# caton-ads1299.net
KiCad netlist of a schematic drawn in Altium Designer
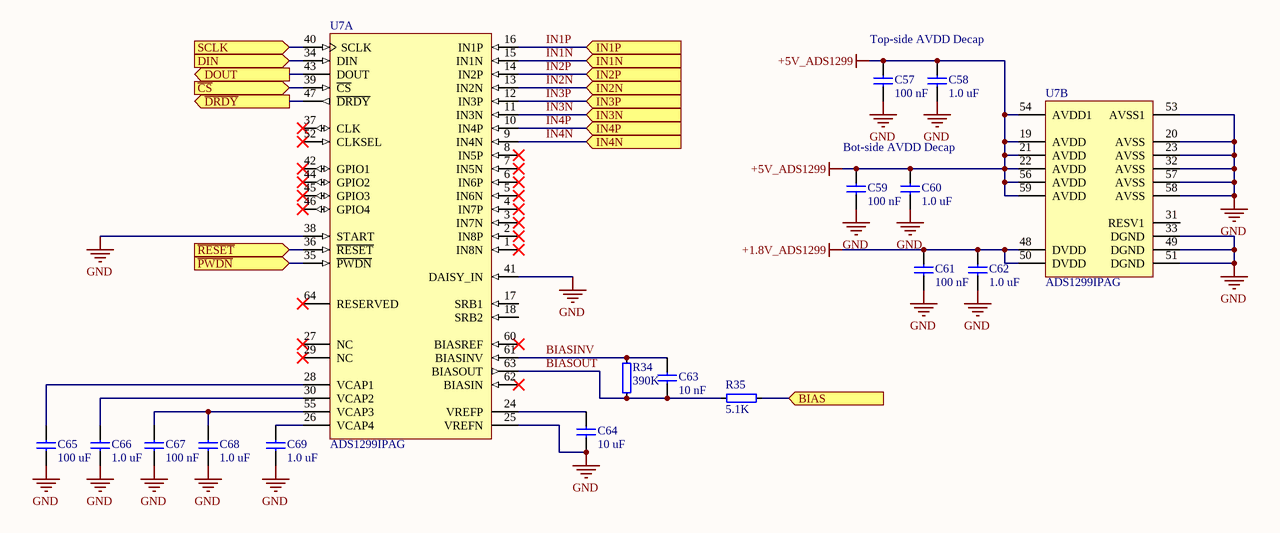
[diagram p0: caton-ads1299.SchDoc]

(export (version "E")
  (design (tool "Eeschema 10.0.6"))
  (components
    (comp (ref "C57")
      (value "100 nF")
      (footprint "BWRC:0402")
      (description "Capacitor, 0402, X5R, ±20%")
      (fields
        (field (name "PART NUMBER") "C0402-4µ7")
        (field (name "MANUFACTURER") "N.A.")
        (field (name "AUTHOR") "rsk")
      )
      (libsource (lib "BSAC") (part "C0402"))
    )
    (comp (ref "C58")
      (value "1.0 uF")
      (footprint "BWRC:0402")
      (description "Capacitor, 0402, X5R, ±20%")
      (fields
        (field (name "PART NUMBER") "C0402-4µ7")
        (field (name "MANUFACTURER") "N.A.")
        (field (name "AUTHOR") "rsk")
      )
      (libsource (lib "BSAC") (part "C0402"))
    )
    (comp (ref "C59")
      (value "100 nF")
      (footprint "BWRC:0402")
      (description "Capacitor, 0402, X5R, ±20%")
      (fields
        (field (name "PART NUMBER") "C0402-4µ7")
        (field (name "MANUFACTURER") "N.A.")
        (field (name "AUTHOR") "rsk")
      )
      (libsource (lib "BSAC") (part "C0402"))
    )
    (comp (ref "C60")
      (value "1.0 uF")
      (footprint "BWRC:0402")
      (description "Capacitor, 0402, X5R, ±20%")
      (fields
        (field (name "PART NUMBER") "C0402-4µ7")
        (field (name "MANUFACTURER") "N.A.")
        (field (name "AUTHOR") "rsk")
      )
      (libsource (lib "BSAC") (part "C0402"))
    )
    (comp (ref "C61")
      (value "100 nF")
      (footprint "BWRC:0402")
      (description "Capacitor, 0402, X5R, ±20%")
      (fields
        (field (name "PART NUMBER") "C0402-4µ7")
        (field (name "MANUFACTURER") "N.A.")
        (field (name "AUTHOR") "rsk")
      )
      (libsource (lib "BSAC") (part "C0402"))
    )
    (comp (ref "C62")
      (value "1.0 uF")
      (footprint "BWRC:0402")
      (description "Capacitor, 0402, X5R, ±20%")
      (fields
        (field (name "PART NUMBER") "C0402-4µ7")
        (field (name "MANUFACTURER") "N.A.")
        (field (name "AUTHOR") "rsk")
      )
      (libsource (lib "BSAC") (part "C0402"))
    )
    (comp (ref "C63")
      (value "10 nF")
      (footprint "BWRC:0402")
      (description "Capacitor, 0402, X5R, ±20%")
      (fields
        (field (name "PART NUMBER") "C0402-4µ7")
        (field (name "MANUFACTURER") "N.A.")
        (field (name "AUTHOR") "rsk")
      )
      (libsource (lib "BSAC") (part "C0402"))
    )
    (comp (ref "C64")
      (value "10 uF")
      (footprint "BWRC:0402")
      (description "Capacitor, 0402, X5R, ±20%")
      (fields
        (field (name "PART NUMBER") "C0402-4µ7")
        (field (name "MANUFACTURER") "N.A.")
        (field (name "AUTHOR") "rsk")
      )
      (libsource (lib "BSAC") (part "C0402"))
    )
    (comp (ref "C65")
      (value "100 uF")
      (footprint "BWRC:0805")
      (description "Capacitor, 0805")
      (fields
        (field (name "PART NUMBER") "C0603-4µ7")
        (field (name "MANUFACTURER") "N.A.")
        (field (name "AUTHOR") "rsk")
      )
      (libsource (lib "BSAC") (part "C0805"))
    )
    (comp (ref "C66")
      (value "1.0 uF")
      (footprint "BWRC:0402")
      (description "Capacitor, 0402, X5R, ±20%")
      (fields
        (field (name "PART NUMBER") "C0402-4µ7")
        (field (name "MANUFACTURER") "N.A.")
        (field (name "AUTHOR") "rsk")
      )
      (libsource (lib "BSAC") (part "C0402"))
    )
    (comp (ref "C67")
      (value "100 nF")
      (footprint "BWRC:0402")
      (description "Capacitor, 0402, X5R, ±20%")
      (fields
        (field (name "PART NUMBER") "C0402-4µ7")
        (field (name "MANUFACTURER") "N.A.")
        (field (name "AUTHOR") "rsk")
      )
      (libsource (lib "BSAC") (part "C0402"))
    )
    (comp (ref "C68")
      (value "1.0 uF")
      (footprint "BWRC:0402")
      (description "Capacitor, 0402, X5R, ±20%")
      (fields
        (field (name "PART NUMBER") "C0402-4µ7")
        (field (name "MANUFACTURER") "N.A.")
        (field (name "AUTHOR") "rsk")
      )
      (libsource (lib "BSAC") (part "C0402"))
    )
    (comp (ref "C69")
      (value "1.0 uF")
      (footprint "BWRC:0402")
      (description "Capacitor, 0402, X5R, ±20%")
      (fields
        (field (name "PART NUMBER") "C0402-4µ7")
        (field (name "MANUFACTURER") "N.A.")
        (field (name "AUTHOR") "rsk")
      )
      (libsource (lib "BSAC") (part "C0402"))
    )
    (comp (ref "R34")
      (value "390K")
      (footprint "BWRC:0402")
      (description "Resistor, 0402, ±1%, 0.05W")
      (fields
        (field (name "PART NUMBER") "R0201-10k")
        (field (name "MANUFACTURER") "N.A.")
        (field (name "AUTHOR") "rsk")
      )
      (libsource (lib "BSAC") (part "R0402"))
    )
    (comp (ref "R35")
      (value "5.1K")
      (footprint "BWRC:0402")
      (description "Resistor, 0402, ±1%, 0.05W")
      (fields
        (field (name "PART NUMBER") "R0201-10k")
        (field (name "MANUFACTURER") "N.A.")
        (field (name "AUTHOR") "rsk")
      )
      (libsource (lib "BSAC") (part "R0402"))
    )
    (comp (ref "U7")
      (value "ADS1299IPAG")
      (footprint "PAG0064A_L")
      (fields (field (name "MANUFACTURER") "Texas Instruments"))
      (libsource (lib "Altium Content Vault") (part "TI-ADS1299-PAG-64"))
    )
  )
  (nets
    (net (code "1") (name "+1.8V_ADS1299") (class "Default")
      (node (ref "C61") (pin "1") (pinfunction "1_1") (pintype "passive"))
      (node (ref "C62") (pin "1") (pinfunction "1_1") (pintype "passive"))
      (node (ref "U7") (pin "48") (pinfunction "DVDD_48") (pintype "power_in"))
      (node (ref "U7") (pin "50") (pinfunction "DVDD_50") (pintype "power_in"))
    )
    (net (code "2") (name "+5V_ADS1299") (class "Default")
      (node (ref "C57") (pin "1") (pinfunction "1_1") (pintype "passive"))
      (node (ref "C58") (pin "1") (pinfunction "1_1") (pintype "passive"))
      (node (ref "C59") (pin "1") (pinfunction "1_1") (pintype "passive"))
      (node (ref "C60") (pin "1") (pinfunction "1_1") (pintype "passive"))
      (node (ref "U7") (pin "19") (pinfunction "AVDD_19") (pintype "power_in"))
      (node (ref "U7") (pin "21") (pinfunction "AVDD_21") (pintype "power_in"))
      (node (ref "U7") (pin "22") (pinfunction "AVDD_22") (pintype "power_in"))
      (node (ref "U7") (pin "54") (pinfunction "AVDD1_54") (pintype "power_in"))
      (node (ref "U7") (pin "56") (pinfunction "AVDD_56") (pintype "power_in"))
      (node (ref "U7") (pin "59") (pinfunction "AVDD_59") (pintype "power_in"))
    )
    (net (code "3") (name "/BIAS") (class "Default")
      (node (ref "R35") (pin "1") (pinfunction "1_1") (pintype "passive"))
    )
    (net (code "4") (name "/BIASINV") (class "Default")
      (node (ref "C63") (pin "1") (pinfunction "1_1") (pintype "passive"))
      (node (ref "R34") (pin "2") (pinfunction "2_2") (pintype "passive"))
      (node (ref "U7") (pin "61") (pinfunction "BIASINV_61") (pintype "input"))
    )
    (net (code "5") (name "/BIASOUT") (class "Default")
      (node (ref "C63") (pin "2") (pinfunction "2_2") (pintype "passive"))
      (node (ref "R34") (pin "1") (pinfunction "1_1") (pintype "passive"))
      (node (ref "R35") (pin "2") (pinfunction "2_2") (pintype "passive"))
      (node (ref "U7") (pin "63") (pinfunction "BIASOUT_63") (pintype "output"))
    )
    (net (code "6") (name "/DIN") (class "Default")
      (node (ref "U7") (pin "34") (pinfunction "DIN_34") (pintype "input"))
    )
    (net (code "7") (name "/DOUT") (class "Default")
      (node (ref "U7") (pin "43") (pinfunction "DOUT_43") (pintype "tri_state"))
    )
    (net (code "8") (name "/IN1N") (class "Default")
      (node (ref "U7") (pin "15") (pinfunction "IN1N_15") (pintype "input"))
    )
    (net (code "9") (name "/IN1P") (class "Default")
      (node (ref "U7") (pin "16") (pinfunction "IN1P_16") (pintype "input"))
    )
    (net (code "10") (name "/IN2N") (class "Default")
      (node (ref "U7") (pin "13") (pinfunction "IN2N_13") (pintype "input"))
    )
    (net (code "11") (name "/IN2P") (class "Default")
      (node (ref "U7") (pin "14") (pinfunction "IN2P_14") (pintype "input"))
    )
    (net (code "12") (name "/IN3N") (class "Default")
      (node (ref "U7") (pin "11") (pinfunction "IN3N_11") (pintype "input"))
    )
    (net (code "13") (name "/IN3P") (class "Default")
      (node (ref "U7") (pin "12") (pinfunction "IN3P_12") (pintype "input"))
    )
    (net (code "14") (name "/IN4N") (class "Default")
      (node (ref "U7") (pin "9") (pinfunction "IN4N_9") (pintype "input"))
    )
    (net (code "15") (name "/IN4P") (class "Default")
      (node (ref "U7") (pin "10") (pinfunction "IN4P_10") (pintype "input"))
    )
    (net (code "16") (name "/SCLK") (class "Default")
      (node (ref "U7") (pin "40") (pinfunction "SCLK_40") (pintype "input"))
    )
    (net (code "17") (name "/~{CS}") (class "Default")
      (node (ref "U7") (pin "39") (pinfunction "~{CS}_39") (pintype "input"))
    )
    (net (code "18") (name "/~{DRDY}") (class "Default")
      (node (ref "U7") (pin "47") (pinfunction "~{DRDY}_47") (pintype "output"))
    )
    (net (code "19") (name "/~{PWDN}") (class "Default")
      (node (ref "U7") (pin "35") (pinfunction "~{PWDN}_35") (pintype "input"))
    )
    (net (code "20") (name "/~{RESET}") (class "Default")
      (node (ref "U7") (pin "36") (pinfunction "~{RESET}_36") (pintype "input"))
    )
    (net (code "21") (name "GND") (class "Default")
      (node (ref "C57") (pin "2") (pinfunction "2_2") (pintype "passive"))
      (node (ref "C58") (pin "2") (pinfunction "2_2") (pintype "passive"))
      (node (ref "C59") (pin "2") (pinfunction "2_2") (pintype "passive"))
      (node (ref "C60") (pin "2") (pinfunction "2_2") (pintype "passive"))
      (node (ref "C61") (pin "2") (pinfunction "2_2") (pintype "passive"))
      (node (ref "C62") (pin "2") (pinfunction "2_2") (pintype "passive"))
      (node (ref "C64") (pin "2") (pinfunction "2_2") (pintype "passive"))
      (node (ref "C65") (pin "2") (pinfunction "2_2") (pintype "passive"))
      (node (ref "C66") (pin "2") (pinfunction "2_2") (pintype "passive"))
      (node (ref "C67") (pin "2") (pinfunction "2_2") (pintype "passive"))
      (node (ref "C68") (pin "2") (pinfunction "2_2") (pintype "passive"))
      (node (ref "C69") (pin "2") (pinfunction "2_2") (pintype "passive"))
      (node (ref "U7") (pin "20") (pinfunction "AVSS_20") (pintype "power_in"))
      (node (ref "U7") (pin "23") (pinfunction "AVSS_23") (pintype "power_in"))
      (node (ref "U7") (pin "25") (pinfunction "VREFN_25") (pintype "passive"))
      (node (ref "U7") (pin "32") (pinfunction "AVSS_32") (pintype "power_in"))
      (node (ref "U7") (pin "33") (pinfunction "DGND_33") (pintype "power_in"))
      (node (ref "U7") (pin "38") (pinfunction "START_38") (pintype "input"))
      (node (ref "U7") (pin "41") (pinfunction "DAISY_IN_41") (pintype "input"))
      (node (ref "U7") (pin "49") (pinfunction "DGND_49") (pintype "power_in"))
      (node (ref "U7") (pin "51") (pinfunction "DGND_51") (pintype "power_in"))
      (node (ref "U7") (pin "53") (pinfunction "AVSS1_53") (pintype "power_in"))
      (node (ref "U7") (pin "57") (pinfunction "AVSS_57") (pintype "power_in"))
      (node (ref "U7") (pin "58") (pinfunction "AVSS_58") (pintype "power_in"))
    )
    (net (code "22") (name "Net-(U7A-VCAP1)") (class "Default")
      (node (ref "C65") (pin "1") (pinfunction "1_1") (pintype "passive"))
      (node (ref "U7") (pin "28") (pinfunction "VCAP1_28") (pintype "passive"))
    )
    (net (code "23") (name "Net-(U7A-VCAP2)") (class "Default")
      (node (ref "C66") (pin "1") (pinfunction "1_1") (pintype "passive"))
      (node (ref "U7") (pin "30") (pinfunction "VCAP2_30") (pintype "passive"))
    )
    (net (code "24") (name "Net-(U7A-VCAP3)") (class "Default")
      (node (ref "C67") (pin "1") (pinfunction "1_1") (pintype "passive"))
      (node (ref "C68") (pin "1") (pinfunction "1_1") (pintype "passive"))
      (node (ref "U7") (pin "55") (pinfunction "VCAP3_55") (pintype "passive"))
    )
    (net (code "25") (name "Net-(U7A-VCAP4)") (class "Default")
      (node (ref "C69") (pin "1") (pinfunction "1_1") (pintype "passive"))
      (node (ref "U7") (pin "26") (pinfunction "VCAP4_26") (pintype "passive"))
    )
    (net (code "26") (name "Net-(U7A-VREFP)") (class "Default")
      (node (ref "C64") (pin "1") (pinfunction "1_1") (pintype "passive"))
      (node (ref "U7") (pin "24") (pinfunction "VREFP_24") (pintype "passive"))
    )
    (net (code "27") (name "unconnected-(U7A-BIASIN-Pad62)") (class "Default")
      (node (ref "U7") (pin "62") (pinfunction "BIASIN_62") (pintype "input+no_connect"))
    )
    (net (code "28") (name "unconnected-(U7A-BIASREF-Pad60)") (class "Default")
      (node (ref "U7") (pin "60") (pinfunction "BIASREF_60") (pintype "input+no_connect"))
    )
    (net (code "29") (name "unconnected-(U7A-CLK-Pad37)") (class "Default")
      (node (ref "U7") (pin "37") (pinfunction "CLK_37") (pintype "bidirectional+no_connect"))
    )
    (net (code "30") (name "unconnected-(U7A-CLKSEL-Pad52)") (class "Default")
      (node (ref "U7") (pin "52") (pinfunction "CLKSEL_52") (pintype "input+no_connect"))
    )
    (net (code "31") (name "unconnected-(U7A-GPIO1-Pad42)") (class "Default")
      (node (ref "U7") (pin "42") (pinfunction "GPIO1_42") (pintype "bidirectional+no_connect"))
    )
    (net (code "32") (name "unconnected-(U7A-GPIO2-Pad44)") (class "Default")
      (node (ref "U7") (pin "44") (pinfunction "GPIO2_44") (pintype "bidirectional+no_connect"))
    )
    (net (code "33") (name "unconnected-(U7A-GPIO3-Pad45)") (class "Default")
      (node (ref "U7") (pin "45") (pinfunction "GPIO3_45") (pintype "bidirectional+no_connect"))
    )
    (net (code "34") (name "unconnected-(U7A-GPIO4-Pad46)") (class "Default")
      (node (ref "U7") (pin "46") (pinfunction "GPIO4_46") (pintype "bidirectional+no_connect"))
    )
    (net (code "35") (name "unconnected-(U7A-IN5N-Pad7)") (class "Default")
      (node (ref "U7") (pin "7") (pinfunction "IN5N_7") (pintype "input+no_connect"))
    )
    (net (code "36") (name "unconnected-(U7A-IN5P-Pad8)") (class "Default")
      (node (ref "U7") (pin "8") (pinfunction "IN5P_8") (pintype "input+no_connect"))
    )
    (net (code "37") (name "unconnected-(U7A-IN6N-Pad5)") (class "Default")
      (node (ref "U7") (pin "5") (pinfunction "IN6N_5") (pintype "input+no_connect"))
    )
    (net (code "38") (name "unconnected-(U7A-IN6P-Pad6)") (class "Default")
      (node (ref "U7") (pin "6") (pinfunction "IN6P_6") (pintype "input+no_connect"))
    )
    (net (code "39") (name "unconnected-(U7A-IN7N-Pad3)") (class "Default")
      (node (ref "U7") (pin "3") (pinfunction "IN7N_3") (pintype "input+no_connect"))
    )
    (net (code "40") (name "unconnected-(U7A-IN7P-Pad4)") (class "Default")
      (node (ref "U7") (pin "4") (pinfunction "IN7P_4") (pintype "input+no_connect"))
    )
    (net (code "41") (name "unconnected-(U7A-IN8N-Pad1)") (class "Default")
      (node (ref "U7") (pin "1") (pinfunction "IN8N_1") (pintype "input+no_connect"))
    )
    (net (code "42") (name "unconnected-(U7A-IN8P-Pad2)") (class "Default")
      (node (ref "U7") (pin "2") (pinfunction "IN8P_2") (pintype "input+no_connect"))
    )
    (net (code "43") (name "unconnected-(U7A-NC-Pad27)") (class "Default")
      (node (ref "U7") (pin "27") (pinfunction "NC_27") (pintype "passive+no_connect"))
    )
    (net (code "44") (name "unconnected-(U7A-NC-Pad29)") (class "Default")
      (node (ref "U7") (pin "29") (pinfunction "NC_29") (pintype "passive+no_connect"))
    )
    (net (code "45") (name "unconnected-(U7A-RESERVED-Pad64)") (class "Default")
      (node (ref "U7") (pin "64") (pinfunction "RESERVED_64") (pintype "passive+no_connect"))
    )
    (net (code "46") (name "unconnected-(U7A-SRB1-Pad17)") (class "Default")
      (node (ref "U7") (pin "17") (pinfunction "SRB1_17") (pintype "input"))
    )
    (net (code "47") (name "unconnected-(U7A-SRB2-Pad18)") (class "Default")
      (node (ref "U7") (pin "18") (pinfunction "SRB2_18") (pintype "input"))
    )
    (net (code "48") (name "unconnected-(U7B-RESV1-Pad31)") (class "Default")
      (node (ref "U7") (pin "31") (pinfunction "RESV1_31") (pintype "power_in"))
    )
  )
)
